# MachSacXa.net
KiCad netlist of a schematic drawn in Altium Designer
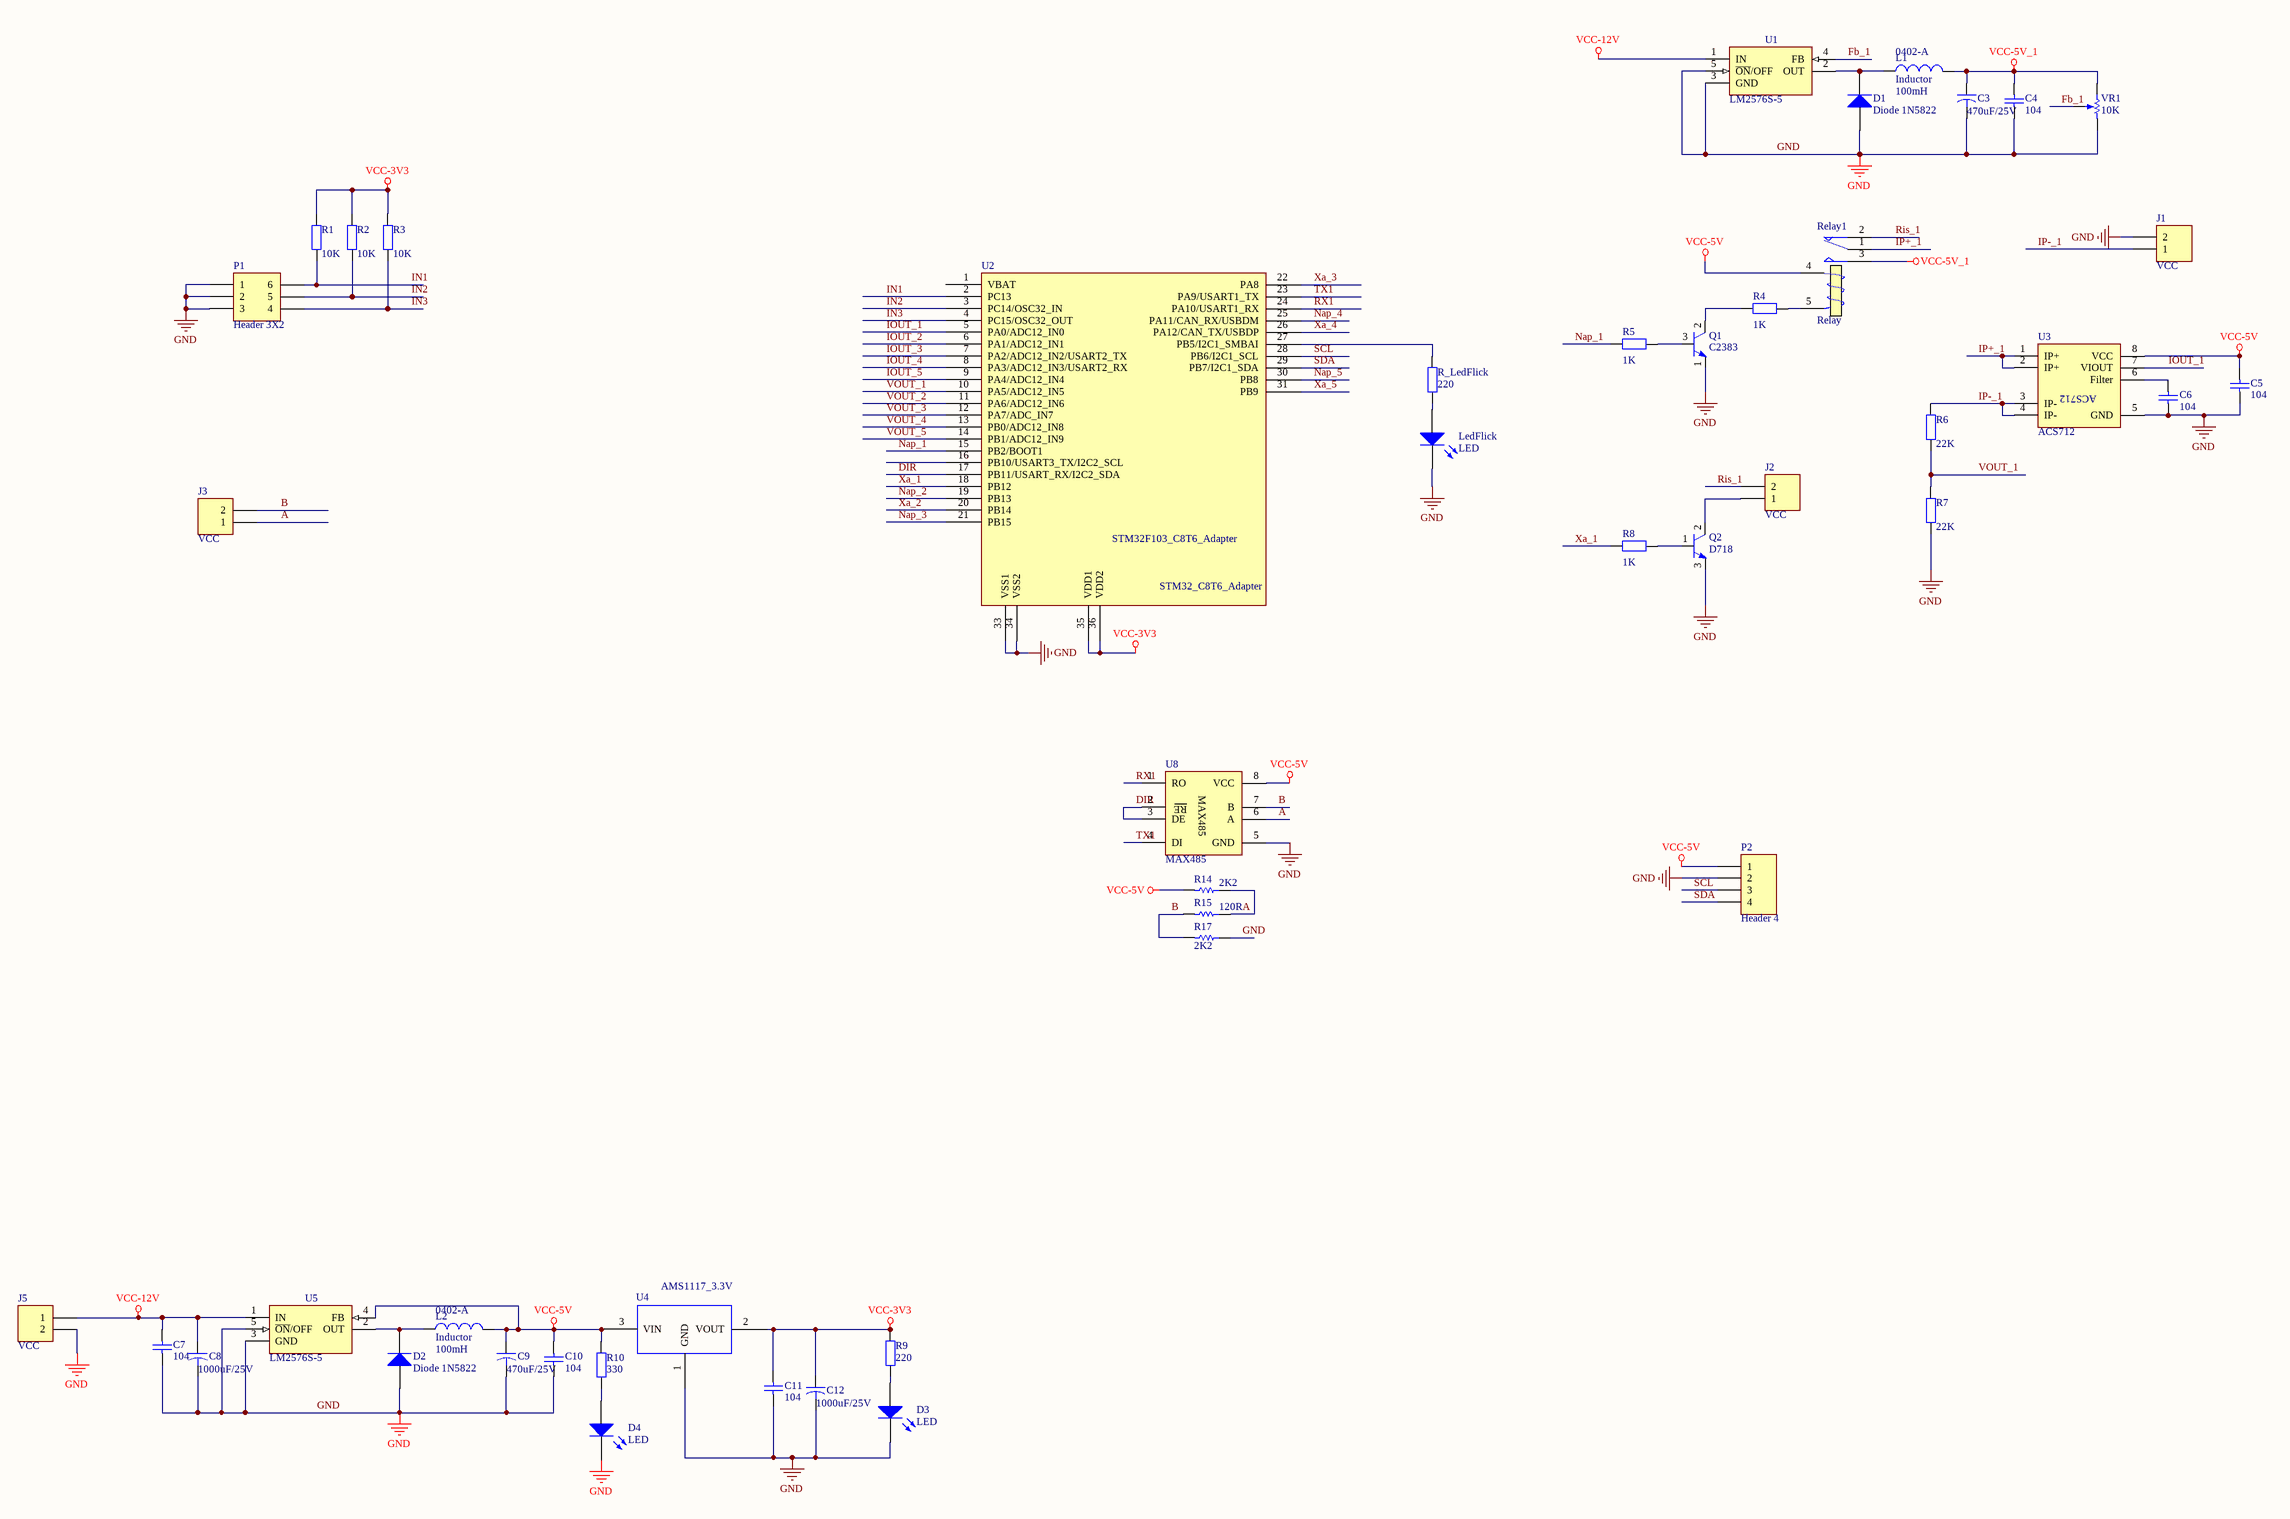
[diagram p0: MachSacXa.SchDoc]

(export (version "E")
  (design (tool "Eeschema 10.0.6"))
  (components
    (comp (ref "C3")
      (value "470uF/25V")
      (footprint "C_D300")
      (description "Capacitor")
      (fields (field (name "PUBLISHER") "Altium Limited"))
      (libsource (lib "Miscellaneous Devices") (part "Cap2"))
    )
    (comp (ref "C4")
      (value "104")
      (footprint "IC_dan:R/C_0805")
      (description "Capacitor")
      (fields (field (name "PUBLISHER") "Altium Limited"))
      (libsource (lib "Miscellaneous Devices") (part "Cap"))
    )
    (comp (ref "C5")
      (value "104")
      (footprint "IC_dan:R/C_0805")
      (description "Capacitor")
      (fields (field (name "PUBLISHER") "Altium Limited"))
      (libsource (lib "Miscellaneous Devices") (part "Cap"))
    )
    (comp (ref "C6")
      (value "104")
      (footprint "IC_dan:R/C_0805")
      (description "Capacitor")
      (fields (field (name "PUBLISHER") "Altium Limited"))
      (libsource (lib "Miscellaneous Devices") (part "Cap"))
    )
    (comp (ref "C7")
      (value "104")
      (footprint "IC_dan:R/C_0805")
      (description "Capacitor")
      (fields (field (name "PUBLISHER") "Altium Limited"))
      (libsource (lib "Miscellaneous Devices") (part "Cap"))
    )
    (comp (ref "C8")
      (value "1000uF/25V")
      (footprint "C_D300")
      (description "Capacitor")
      (fields (field (name "PUBLISHER") "Altium Limited"))
      (libsource (lib "Miscellaneous Devices") (part "Cap2"))
    )
    (comp (ref "C9")
      (value "470uF/25V")
      (footprint "C_D300")
      (description "Capacitor")
      (fields (field (name "PUBLISHER") "Altium Limited"))
      (libsource (lib "Miscellaneous Devices") (part "Cap2"))
    )
    (comp (ref "C10")
      (value "104")
      (footprint "IC_dan:R/C_0805")
      (description "Capacitor")
      (fields (field (name "PUBLISHER") "Altium Limited"))
      (libsource (lib "Miscellaneous Devices") (part "Cap"))
    )
    (comp (ref "C11")
      (value "104")
      (footprint "IC_dan:R/C_0805")
      (description "Capacitor")
      (fields (field (name "PUBLISHER") "Altium Limited"))
      (libsource (lib "Miscellaneous Devices") (part "Cap"))
    )
    (comp (ref "C12")
      (value "1000uF/25V")
      (footprint "C_D300")
      (description "Capacitor")
      (fields (field (name "PUBLISHER") "Altium Limited"))
      (libsource (lib "Miscellaneous Devices") (part "Cap2"))
    )
    (comp (ref "D1")
      (value "Diode 1N5822")
      (footprint "Diode_1A")
      (description "1 Amp General Purpose Rectifier")
      (fields (field (name "PUBLISHER") "Altium Limited"))
      (libsource (lib "Miscellaneous Devices") (part "Diode 1N4004"))
    )
    (comp (ref "D2")
      (value "Diode 1N5822")
      (footprint "Diode_1A")
      (description "1 Amp General Purpose Rectifier")
      (fields (field (name "PUBLISHER") "Altium Limited"))
      (libsource (lib "Miscellaneous Devices") (part "Diode 1N4004"))
    )
    (comp (ref "D3")
      (value "LED")
      (footprint "IC_dan:LED_SMD (0805)")
      (description "Typical INFRARED GaAs LED")
      (fields (field (name "PUBLISHER") "Altium Limited"))
      (libsource (lib "Miscellaneous Devices") (part "LED0"))
    )
    (comp (ref "D4")
      (value "LED")
      (footprint "LED_SMD (0805)")
      (description "Typical INFRARED GaAs LED")
      (fields (field (name "PUBLISHER") "Altium Limited"))
      (libsource (lib "Miscellaneous Devices") (part "LED0"))
    )
    (comp (ref "J1")
      (value "VCC")
      (footprint "HEADER1_2(400)")
      (description "Header, 2-Pin")
      (fields (field (name "PUBLISHER") "Altium Limited"))
      (libsource (lib "Miscellaneous Connectors") (part "Header 2"))
    )
    (comp (ref "J2")
      (value "VCC")
      (footprint "HEADER1_2(400)")
      (description "Header, 2-Pin")
      (fields (field (name "PUBLISHER") "Altium Limited"))
      (libsource (lib "Miscellaneous Connectors") (part "Header 2"))
    )
    (comp (ref "J3")
      (value "VCC")
      (footprint "HEADER1_2(400)")
      (description "Header, 2-Pin")
      (fields (field (name "PUBLISHER") "Altium Limited"))
      (libsource (lib "") (part "Header 2_2"))
    )
    (comp (ref "J5")
      (value "VCC")
      (footprint "HEADER1_2(400)")
      (description "Header, 2-Pin")
      (fields (field (name "PUBLISHER") "Altium Limited"))
      (libsource (lib "") (part "Header 2_1"))
    )
    (comp (ref "L1")
      (value "Inductor")
      (footprint "Cuon_cam(100mH)")
      (fields
        (field (name "PACKAGEREFERENCE") "0402-A")
        (field (name "ALTIUM_VALUE") "100mH")
        (field (name "PUBLISHER") "Altium Limited")
      )
      (libsource (lib "Miscellaneous Devices") (part "Inductor"))
    )
    (comp (ref "L2")
      (value "Inductor")
      (footprint "Cuon_cam(100mH)")
      (fields
        (field (name "PACKAGEREFERENCE") "0402-A")
        (field (name "ALTIUM_VALUE") "100mH")
        (field (name "PUBLISHER") "Altium Limited")
      )
      (libsource (lib "Miscellaneous Devices") (part "Inductor"))
    )
    (comp (ref "LedFlick")
      (value "LED")
      (footprint "IC_dan:LED_SMD (0805)")
      (description "Typical INFRARED GaAs LED")
      (fields (field (name "PUBLISHER") "Altium Limited"))
      (libsource (lib "Miscellaneous Devices") (part "LED0"))
    )
    (comp (ref "P1")
      (value "Header 3X2")
      (footprint "DIP6_300")
      (description "Header, 3-Pin, Dual row")
      (fields (field (name "PUBLISHER") "Altium Limited"))
      (libsource (lib "Connectors") (part "Header 3X2"))
    )
    (comp (ref "P2")
      (value "Header 4")
      (footprint "CON-Trang1_4")
      (description "Header, 4-Pin")
      (fields (field (name "PUBLISHER") "Altium Limited"))
      (libsource (lib "Connectors") (part "Header 4"))
    )
    (comp (ref "Q1")
      (value "C2383")
      (footprint "C1815/C945")
      (fields (field (name "Comment") "TR_NPN_ECB"))
      (libsource (lib "DEVICE") (part "TR_NPN_ECB"))
    )
    (comp (ref "Q2")
      (value "D718")
      (footprint "D718")
      (fields (field (name "Comment") "TR_NPN_D718"))
      (libsource (lib "DEVICE") (part "TR_NPN_D718"))
    )
    (comp (ref "R1")
      (value "10K")
      (footprint "R/C_0805")
      (description "Resistor")
      (fields (field (name "PUBLISHER") "Altium Limited"))
      (libsource (lib "") (part "Res2_1"))
    )
    (comp (ref "R2")
      (value "10K")
      (footprint "R/C_0805")
      (description "Resistor")
      (fields (field (name "PUBLISHER") "Altium Limited"))
      (libsource (lib "") (part "Res2_1"))
    )
    (comp (ref "R3")
      (value "10K")
      (footprint "R/C_0805")
      (description "Resistor")
      (fields (field (name "PUBLISHER") "Altium Limited"))
      (libsource (lib "") (part "Res2_1"))
    )
    (comp (ref "R4")
      (value "1K")
      (footprint "R/C_0805")
      (description "Resistor")
      (fields (field (name "PUBLISHER") "Altium Limited"))
      (libsource (lib "Miscellaneous Devices") (part "Res2"))
    )
    (comp (ref "R5")
      (value "1K")
      (footprint "R/C_0805")
      (description "Resistor")
      (fields (field (name "PUBLISHER") "Altium Limited"))
      (libsource (lib "Miscellaneous Devices") (part "Res2"))
    )
    (comp (ref "R6")
      (value "22K")
      (footprint "R/C_0805")
      (description "Resistor")
      (fields (field (name "PUBLISHER") "Altium Limited"))
      (libsource (lib "") (part "Res2_1"))
    )
    (comp (ref "R7")
      (value "22K")
      (footprint "R/C_0805")
      (description "Resistor")
      (fields (field (name "PUBLISHER") "Altium Limited"))
      (libsource (lib "") (part "Res2_1"))
    )
    (comp (ref "R8")
      (value "1K")
      (footprint "R/C_0805")
      (description "Resistor")
      (fields (field (name "PUBLISHER") "Altium Limited"))
      (libsource (lib "Miscellaneous Devices") (part "Res2"))
    )
    (comp (ref "R9")
      (value "220")
      (footprint "R/C_0805")
      (description "Resistor")
      (fields (field (name "PUBLISHER") "Altium Limited"))
      (libsource (lib "") (part "Res2_2"))
    )
    (comp (ref "R10")
      (value "330")
      (footprint "R/C_0805")
      (description "Resistor")
      (fields (field (name "PUBLISHER") "Altium Limited"))
      (libsource (lib "") (part "Res2_2"))
    )
    (comp (ref "R14")
      (value "2K2")
      (footprint "R/C_0805")
      (description "Resistor")
      (fields (field (name "Comment") "Res1") (field (name "PUBLISHER") "Altium Limited"))
      (libsource (lib "Miscellaneous Devices") (part "Res1"))
    )
    (comp (ref "R15")
      (value "120R")
      (footprint "R/C_0805")
      (description "Resistor")
      (fields (field (name "Comment") "Res1") (field (name "PUBLISHER") "Altium Limited"))
      (libsource (lib "Miscellaneous Devices") (part "Res1"))
    )
    (comp (ref "R17")
      (value "2K2")
      (footprint "R/C_0805")
      (description "Resistor")
      (fields (field (name "Comment") "Res1") (field (name "PUBLISHER") "Altium Limited"))
      (libsource (lib "Miscellaneous Devices") (part "Res1"))
    )
    (comp (ref "Relay1")
      (value "Relay")
      (footprint "RL5P_12V7A")
      (description "SPDT Relay")
      (fields (field (name "PUBLISHER") "Altium Limited"))
      (libsource (lib "DEVICE") (part "Relay"))
    )
    (comp (ref "R_LedFlick")
      (value "220")
      (footprint "R/C_0805")
      (description "Resistor")
      (fields (field (name "PUBLISHER") "Altium Limited"))
      (libsource (lib "") (part "Res2_2"))
    )
    (comp (ref "U1")
      (value "LM2576S-5")
      (footprint "THROUGH HOLES:LM2576")
      (description "Simple Switcher 3A Step Down Voltage Regulator")
      (fields (field (name "PUBLISHER") "Altium Limited"))
      (libsource (lib "NSC Power Mgt Switching Regulator") (part "LM2576S-5.0"))
    )
    (comp (ref "U2")
      (value "STM32F103_C8T6_Adapter")
      (footprint "Dip36(9x4)")
      (libsource (lib "DEVICE") (part "STM32_C8T6_Adapter"))
    )
    (comp (ref "U3") (value "ACS712") (footprint "DS1307") (libsource (lib "DEVICE") (part "ACS712")))
    (comp (ref "U4")
      (value "AMS1117_3.3V")
      (footprint "AMS1117_(SOT_223)")
      (libsource (lib "DEVICE") (part "AMS1117_3.3V"))
    )
    (comp (ref "U5")
      (value "LM2576S-5")
      (footprint "LM2576")
      (description "Simple Switcher 3A Step Down Voltage Regulator")
      (fields (field (name "PUBLISHER") "Altium Limited"))
      (libsource (lib "NSC Power Mgt Switching Regulator") (part "LM2576S-5.0"))
    )
    (comp (ref "U8") (value "MAX485") (footprint "DIP8_300") (libsource (lib "DEVICE") (part "MAX485")))
    (comp (ref "VR1")
      (value "10K")
      (footprint "VR_3")
      (fields (field (name "Comment") "Bien tro"))
      (libsource (lib "DEVICE") (part "VR"))
    )
  )
  (nets
    (net (code "1") (name "/A") (class "Default")
      (node (ref "J3") (pin "1") (pinfunction "1_1") (pintype "passive"))
      (node (ref "R14") (pin "1") (pinfunction "1_1") (pintype "passive"))
      (node (ref "R15") (pin "1") (pinfunction "1_1") (pintype "passive"))
      (node (ref "U8") (pin "6") (pinfunction "A_6") (pintype "passive"))
    )
    (net (code "2") (name "/B") (class "Default")
      (node (ref "J3") (pin "2") (pinfunction "2_2") (pintype "passive"))
      (node (ref "R15") (pin "2") (pinfunction "2_2") (pintype "passive"))
      (node (ref "R17") (pin "2") (pinfunction "2_2") (pintype "passive"))
      (node (ref "U8") (pin "7") (pinfunction "B_7") (pintype "passive"))
    )
    (net (code "3") (name "/DIR") (class "Default")
      (node (ref "U2") (pin "17") (pinfunction "PB11/USART_RX/I2C2_SDA_17") (pintype "passive"))
      (node (ref "U8") (pin "2") (pinfunction "2_2") (pintype "passive"))
      (node (ref "U8") (pin "3") (pinfunction "DE_3") (pintype "passive"))
    )
    (net (code "4") (name "/Fb_1") (class "Default")
      (node (ref "U1") (pin "4") (pinfunction "FB_4") (pintype "input"))
      (node (ref "VR1") (pin "2") (pinfunction "BOT_2") (pintype "passive"))
    )
    (net (code "5") (name "/IN1") (class "Default")
      (node (ref "P1") (pin "6") (pinfunction "6_6") (pintype "passive"))
      (node (ref "R1") (pin "1") (pinfunction "1_1") (pintype "passive"))
      (node (ref "U2") (pin "2") (pinfunction "PC13_2") (pintype "passive"))
    )
    (net (code "6") (name "/IN2") (class "Default")
      (node (ref "P1") (pin "5") (pinfunction "5_5") (pintype "passive"))
      (node (ref "R2") (pin "1") (pinfunction "1_1") (pintype "passive"))
      (node (ref "U2") (pin "3") (pinfunction "PC14/OSC32_IN_3") (pintype "passive"))
    )
    (net (code "7") (name "/IN3") (class "Default")
      (node (ref "P1") (pin "4") (pinfunction "4_4") (pintype "passive"))
      (node (ref "R3") (pin "1") (pinfunction "1_1") (pintype "passive"))
      (node (ref "U2") (pin "4") (pinfunction "PC15/OSC32_OUT_4") (pintype "passive"))
    )
    (net (code "8") (name "/IOUT_1") (class "Default")
      (node (ref "U2") (pin "5") (pinfunction "PA0/ADC12_IN0_5") (pintype "passive"))
      (node (ref "U3") (pin "7") (pinfunction "VIOUT_7") (pintype "passive"))
    )
    (net (code "9") (name "/IOUT_2") (class "Default")
      (node (ref "U2") (pin "6") (pinfunction "PA1/ADC12_IN1_6") (pintype "passive"))
    )
    (net (code "10") (name "/IOUT_3") (class "Default")
      (node (ref "U2") (pin "7") (pinfunction "PA2/ADC12_IN2/USART2_TX_7") (pintype "passive"))
    )
    (net (code "11") (name "/IOUT_4") (class "Default")
      (node (ref "U2") (pin "8") (pinfunction "PA3/ADC12_IN3/USART2_RX_8") (pintype "passive"))
    )
    (net (code "12") (name "/IOUT_5") (class "Default")
      (node (ref "U2") (pin "9") (pinfunction "PA4/ADC12_IN4_9") (pintype "passive"))
    )
    (net (code "13") (name "/IP+_1") (class "Default")
      (node (ref "Relay1") (pin "1") (pinfunction "COM_1") (pintype "passive"))
      (node (ref "U3") (pin "1") (pinfunction "IP+_1") (pintype "passive"))
      (node (ref "U3") (pin "2") (pinfunction "IP+_2") (pintype "passive"))
    )
    (net (code "14") (name "/IP-_1") (class "Default")
      (node (ref "J1") (pin "1") (pinfunction "1_1") (pintype "passive"))
      (node (ref "R6") (pin "2") (pinfunction "2_2") (pintype "passive"))
      (node (ref "U3") (pin "3") (pinfunction "IP-_3") (pintype "passive"))
      (node (ref "U3") (pin "4") (pinfunction "IP-_4") (pintype "passive"))
    )
    (net (code "15") (name "/Nap_1") (class "Default")
      (node (ref "R5") (pin "1") (pinfunction "1_1") (pintype "passive"))
      (node (ref "U2") (pin "15") (pinfunction "PB2/BOOT1_15") (pintype "passive"))
    )
    (net (code "16") (name "/Nap_2") (class "Default")
      (node (ref "U2") (pin "19") (pinfunction "PB13_19") (pintype "passive"))
    )
    (net (code "17") (name "/Nap_3") (class "Default")
      (node (ref "U2") (pin "21") (pinfunction "PB15_21") (pintype "passive"))
    )
    (net (code "18") (name "/Nap_4") (class "Default")
      (node (ref "U2") (pin "25") (pinfunction "PA11/CAN_RX/USBDM_25") (pintype "passive"))
    )
    (net (code "19") (name "/Nap_5") (class "Default")
      (node (ref "U2") (pin "30") (pinfunction "PB8_30") (pintype "passive"))
    )
    (net (code "20") (name "/RX1") (class "Default")
      (node (ref "U2") (pin "24") (pinfunction "PA10/USART1_RX_24") (pintype "passive"))
      (node (ref "U8") (pin "1") (pinfunction "RO_1") (pintype "passive"))
    )
    (net (code "21") (name "/Ris_1") (class "Default")
      (node (ref "J2") (pin "2") (pinfunction "2_2") (pintype "passive"))
      (node (ref "Relay1") (pin "2") (pinfunction "NC_2") (pintype "passive"))
    )
    (net (code "22") (name "/SCL") (class "Default")
      (node (ref "P2") (pin "3") (pinfunction "3_3") (pintype "passive"))
      (node (ref "U2") (pin "28") (pinfunction "PB6/I2C1_SCL_28") (pintype "passive"))
    )
    (net (code "23") (name "/SDA") (class "Default")
      (node (ref "P2") (pin "4") (pinfunction "4_4") (pintype "passive"))
      (node (ref "U2") (pin "29") (pinfunction "PB7/I2C1_SDA_29") (pintype "passive"))
    )
    (net (code "24") (name "/TX1") (class "Default")
      (node (ref "U2") (pin "23") (pinfunction "PA9/USART1_TX_23") (pintype "passive"))
      (node (ref "U8") (pin "4") (pinfunction "DI_4") (pintype "passive"))
    )
    (net (code "25") (name "/VOUT_1") (class "Default")
      (node (ref "R6") (pin "1") (pinfunction "1_1") (pintype "passive"))
      (node (ref "R7") (pin "2") (pinfunction "2_2") (pintype "passive"))
      (node (ref "U2") (pin "10") (pinfunction "PA5/ADC12_IN5_10") (pintype "passive"))
    )
    (net (code "26") (name "/VOUT_2") (class "Default")
      (node (ref "U2") (pin "11") (pinfunction "PA6/ADC12_IN6_11") (pintype "passive"))
    )
    (net (code "27") (name "/VOUT_3") (class "Default")
      (node (ref "U2") (pin "12") (pinfunction "PA7/ADC_IN7_12") (pintype "passive"))
    )
    (net (code "28") (name "/VOUT_4") (class "Default")
      (node (ref "U2") (pin "13") (pinfunction "PB0/ADC12_IN8_13") (pintype "passive"))
    )
    (net (code "29") (name "/VOUT_5") (class "Default")
      (node (ref "U2") (pin "14") (pinfunction "PB1/ADC12_IN9_14") (pintype "passive"))
    )
    (net (code "30") (name "/Xa_1") (class "Default")
      (node (ref "R8") (pin "1") (pinfunction "1_1") (pintype "passive"))
      (node (ref "U2") (pin "18") (pinfunction "PB12_18") (pintype "passive"))
    )
    (net (code "31") (name "/Xa_2") (class "Default")
      (node (ref "U2") (pin "20") (pinfunction "PB14_20") (pintype "passive"))
    )
    (net (code "32") (name "/Xa_3") (class "Default")
      (node (ref "U2") (pin "22") (pinfunction "PA8_22") (pintype "passive"))
    )
    (net (code "33") (name "/Xa_4") (class "Default")
      (node (ref "U2") (pin "26") (pinfunction "PA12/CAN_TX/USBDP_26") (pintype "passive"))
    )
    (net (code "34") (name "/Xa_5") (class "Default")
      (node (ref "U2") (pin "31") (pinfunction "PB9_31") (pintype "passive"))
    )
    (net (code "35") (name "GND") (class "Default")
      (node (ref "C10") (pin "2") (pinfunction "2_2") (pintype "passive"))
      (node (ref "C11") (pin "2") (pinfunction "2_2") (pintype "passive"))
      (node (ref "C12") (pin "2") (pinfunction "2_2") (pintype "passive"))
      (node (ref "C3") (pin "2") (pinfunction "2_2") (pintype "passive"))
      (node (ref "C4") (pin "2") (pinfunction "2_2") (pintype "passive"))
      (node (ref "C5") (pin "2") (pinfunction "2_2") (pintype "passive"))
      (node (ref "C6") (pin "2") (pinfunction "2_2") (pintype "passive"))
      (node (ref "C7") (pin "2") (pinfunction "2_2") (pintype "passive"))
      (node (ref "C8") (pin "2") (pinfunction "2_2") (pintype "passive"))
      (node (ref "C9") (pin "2") (pinfunction "2_2") (pintype "passive"))
      (node (ref "D1") (pin "1") (pinfunction "A_1") (pintype "passive"))
      (node (ref "D2") (pin "1") (pinfunction "A_1") (pintype "passive"))
      (node (ref "D3") (pin "2") (pinfunction "K_2") (pintype "passive"))
      (node (ref "D4") (pin "2") (pinfunction "K_2") (pintype "passive"))
      (node (ref "J1") (pin "2") (pinfunction "2_2") (pintype "passive"))
      (node (ref "J5") (pin "2") (pinfunction "2_2") (pintype "passive"))
      (node (ref "LedFlick") (pin "2") (pinfunction "K_2") (pintype "passive"))
      (node (ref "P1") (pin "1") (pinfunction "1_1") (pintype "passive"))
      (node (ref "P1") (pin "2") (pinfunction "2_2") (pintype "passive"))
      (node (ref "P1") (pin "3") (pinfunction "3_3") (pintype "passive"))
      (node (ref "P2") (pin "2") (pinfunction "2_2") (pintype "passive"))
      (node (ref "Q1") (pin "1") (pinfunction "E_1") (pintype "passive"))
      (node (ref "Q2") (pin "3") (pinfunction "B_3") (pintype "passive"))
      (node (ref "R17") (pin "1") (pinfunction "1_1") (pintype "passive"))
      (node (ref "R7") (pin "1") (pinfunction "1_1") (pintype "passive"))
      (node (ref "U1") (pin "3") (pinfunction "GND_3") (pintype "power_in"))
      (node (ref "U1") (pin "5") (pinfunction "~{ON}/OFF_5") (pintype "input"))
      (node (ref "U2") (pin "33") (pinfunction "VSS1_33") (pintype "passive"))
      (node (ref "U2") (pin "34") (pinfunction "VSS2_34") (pintype "passive"))
      (node (ref "U3") (pin "5") (pinfunction "GND_5") (pintype "passive"))
      (node (ref "U4") (pin "1") (pinfunction "GND_1") (pintype "passive"))
      (node (ref "U5") (pin "3") (pinfunction "GND_3") (pintype "power_in"))
      (node (ref "U5") (pin "5") (pinfunction "~{ON}/OFF_5") (pintype "input"))
      (node (ref "U8") (pin "5") (pinfunction "GND_5") (pintype "passive"))
      (node (ref "VR1") (pin "3") (pinfunction "TAP_3") (pintype "passive"))
    )
    (net (code "36") (name "Net-(D1-K)") (class "Default")
      (node (ref "D1") (pin "2") (pinfunction "K_2") (pintype "passive"))
      (node (ref "L1") (pin "1") (pinfunction "1_1") (pintype "passive"))
      (node (ref "U1") (pin "2") (pinfunction "OUT_2") (pintype "power_in"))
    )
    (net (code "37") (name "Net-(D2-K)") (class "Default")
      (node (ref "D2") (pin "2") (pinfunction "K_2") (pintype "passive"))
      (node (ref "L2") (pin "1") (pinfunction "1_1") (pintype "passive"))
      (node (ref "U5") (pin "2") (pinfunction "OUT_2") (pintype "power_in"))
    )
    (net (code "38") (name "Net-(D3-A)") (class "Default")
      (node (ref "D3") (pin "1") (pinfunction "A_1") (pintype "passive"))
      (node (ref "R9") (pin "2") (pinfunction "2_2") (pintype "passive"))
    )
    (net (code "39") (name "Net-(D4-A)") (class "Default")
      (node (ref "D4") (pin "1") (pinfunction "A_1") (pintype "passive"))
      (node (ref "R10") (pin "2") (pinfunction "2_2") (pintype "passive"))
    )
    (net (code "40") (name "Net-(LedFlick-A)") (class "Default")
      (node (ref "LedFlick") (pin "1") (pinfunction "A_1") (pintype "passive"))
      (node (ref "R_LedFlick") (pin "2") (pinfunction "2_2") (pintype "passive"))
    )
    (net (code "41") (name "Net-(Q1-B)") (class "Default")
      (node (ref "Q1") (pin "3") (pinfunction "B_3") (pintype "passive"))
      (node (ref "R5") (pin "2") (pinfunction "2_2") (pintype "passive"))
    )
    (net (code "42") (name "Net-(Q1-C)") (class "Default")
      (node (ref "Q1") (pin "2") (pinfunction "C_2") (pintype "passive"))
      (node (ref "R4") (pin "1") (pinfunction "1_1") (pintype "passive"))
    )
    (net (code "43") (name "Net-(Q2-C)") (class "Default")
      (node (ref "J2") (pin "1") (pinfunction "1_1") (pintype "passive"))
      (node (ref "Q2") (pin "2") (pinfunction "C_2") (pintype "passive"))
    )
    (net (code "44") (name "Net-(Q2-E)") (class "Default")
      (node (ref "Q2") (pin "1") (pinfunction "E_1") (pintype "passive"))
      (node (ref "R8") (pin "2") (pinfunction "2_2") (pintype "passive"))
    )
    (net (code "45") (name "Net-(Relay1-T2)") (class "Default")
      (node (ref "R4") (pin "2") (pinfunction "2_2") (pintype "passive"))
      (node (ref "Relay1") (pin "5") (pinfunction "T2_5") (pintype "passive"))
    )
    (net (code "46") (name "Net-(U2-PB5{slash}I2C1_SMBAI)") (class "Default")
      (node (ref "R_LedFlick") (pin "1") (pinfunction "1_1") (pintype "passive"))
      (node (ref "U2") (pin "27") (pinfunction "PB5/I2C1_SMBAI_27") (pintype "passive"))
    )
    (net (code "47") (name "Net-(U3-Filter)") (class "Default")
      (node (ref "C6") (pin "1") (pinfunction "1_1") (pintype "passive"))
      (node (ref "U3") (pin "6") (pinfunction "Filter_6") (pintype "passive"))
    )
    (net (code "48") (name "VCC-3V3") (class "Default")
      (node (ref "C11") (pin "1") (pinfunction "1_1") (pintype "passive"))
      (node (ref "C12") (pin "1") (pinfunction "1_1") (pintype "passive"))
      (node (ref "R1") (pin "2") (pinfunction "2_2") (pintype "passive"))
      (node (ref "R2") (pin "2") (pinfunction "2_2") (pintype "passive"))
      (node (ref "R3") (pin "2") (pinfunction "2_2") (pintype "passive"))
      (node (ref "R9") (pin "1") (pinfunction "1_1") (pintype "passive"))
      (node (ref "U2") (pin "35") (pinfunction "VDD1_35") (pintype "passive"))
      (node (ref "U2") (pin "36") (pinfunction "VDD2_36") (pintype "passive"))
      (node (ref "U4") (pin "2") (pinfunction "VOUT_2") (pintype "passive"))
    )
    (net (code "49") (name "VCC-5V") (class "Default")
      (node (ref "C10") (pin "1") (pinfunction "1_1") (pintype "passive"))
      (node (ref "C5") (pin "1") (pinfunction "1_1") (pintype "passive"))
      (node (ref "C9") (pin "1") (pinfunction "1_1") (pintype "passive"))
      (node (ref "L2") (pin "2") (pinfunction "2_2") (pintype "passive"))
      (node (ref "P2") (pin "1") (pinfunction "1_1") (pintype "passive"))
      (node (ref "R10") (pin "1") (pinfunction "1_1") (pintype "passive"))
      (node (ref "R14") (pin "2") (pinfunction "2_2") (pintype "passive"))
      (node (ref "Relay1") (pin "4") (pinfunction "T1_4") (pintype "passive"))
      (node (ref "U3") (pin "8") (pinfunction "VCC_8") (pintype "passive"))
      (node (ref "U4") (pin "3") (pinfunction "VIN_3") (pintype "passive"))
      (node (ref "U5") (pin "4") (pinfunction "FB_4") (pintype "input"))
      (node (ref "U8") (pin "8") (pinfunction "VCC_8") (pintype "passive"))
    )
    (net (code "50") (name "VCC-5V_1") (class "Default")
      (node (ref "C3") (pin "1") (pinfunction "1_1") (pintype "passive"))
      (node (ref "C4") (pin "1") (pinfunction "1_1") (pintype "passive"))
      (node (ref "L1") (pin "2") (pinfunction "2_2") (pintype "passive"))
      (node (ref "Relay1") (pin "3") (pinfunction "NO_3") (pintype "passive"))
      (node (ref "VR1") (pin "1") (pinfunction "TOP_1") (pintype "passive"))
    )
    (net (code "51") (name "VCC-12V") (class "Default")
      (node (ref "C7") (pin "1") (pinfunction "1_1") (pintype "passive"))
      (node (ref "C8") (pin "1") (pinfunction "1_1") (pintype "passive"))
      (node (ref "J5") (pin "1") (pinfunction "1_1") (pintype "passive"))
      (node (ref "U1") (pin "1") (pinfunction "IN_1") (pintype "power_in"))
      (node (ref "U5") (pin "1") (pinfunction "IN_1") (pintype "power_in"))
    )
    (net (code "52") (name "unconnected-(U2-PB10{slash}USART3_TX{slash}I2C2_SCL-Pad16)") (class "Default")
      (node (ref "U2") (pin "16") (pinfunction "PB10/USART3_TX/I2C2_SCL_16") (pintype "passive"))
    )
    (net (code "53") (name "unconnected-(U2-VBAT-Pad1)") (class "Default")
      (node (ref "U2") (pin "1") (pinfunction "VBAT_1") (pintype "passive"))
    )
  )
)
